# Sheet1.net
KiCad netlist of a schematic drawn in Altium Designer
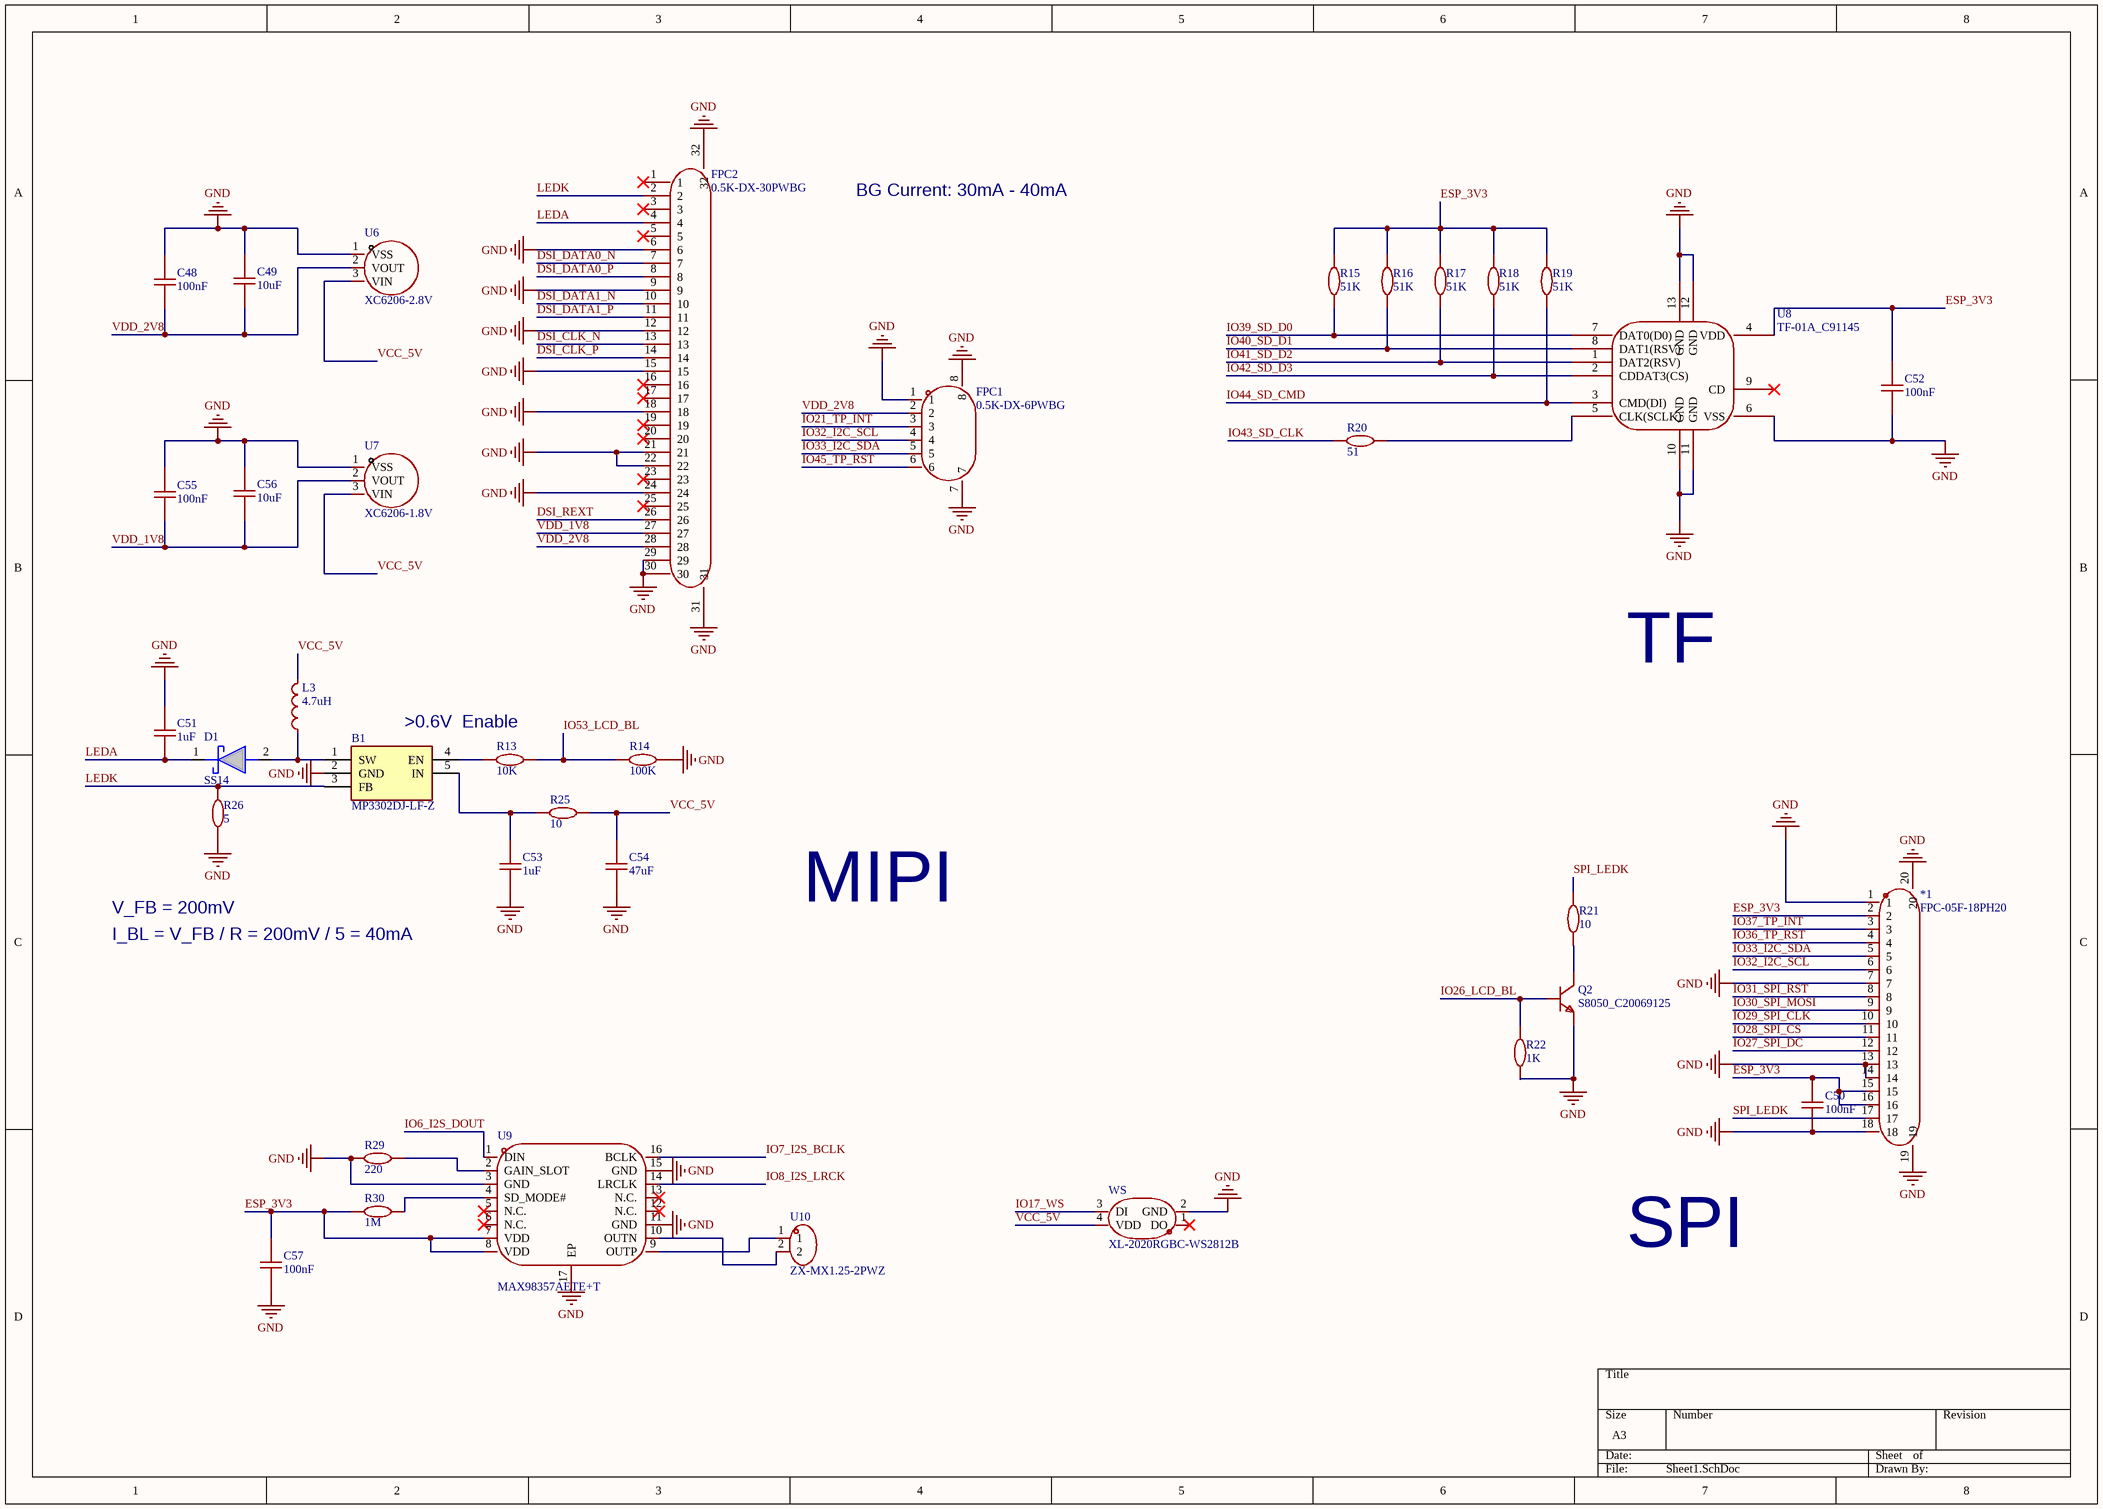
[diagram p0: Sheet1.SchDoc]

(export (version "E")
  (design (tool "Eeschema 10.0.6"))
  (components
    (comp (ref "*1")
      (value "FPC-05F-18PH20")
      (footprint "FPC-SMD_18P-P0.50_FPC-05F-18PH20")
      (libsource (lib "Connector") (part "FPC-05F-18PH20"))
    )
    (comp (ref "B1")
      (value "MP3302DJ-LF-Z")
      (footprint "SOT95P280X100-5N")
      (description "LED Lighting Drivers 1.3A, 1.3MHz WLED Driver")
      (fields (field (name "MOUSER PART NUMBER") "946-MP3302DJLFZ"))
      (libsource (lib "IC") (part "MP3302DJ-LF-Z"))
    )
    (comp (ref "C48") (value "100nF") (footprint "C0402") (libsource (lib "RLC") (part "C0402")))
    (comp (ref "C49") (value "10uF") (footprint "C0603") (libsource (lib "RLC") (part "C0603")))
    (comp (ref "C50") (value "100nF") (footprint "C0402") (libsource (lib "RLC") (part "C0402")))
    (comp (ref "C51") (value "1uF") (footprint "C0402") (libsource (lib "RLC") (part "C0402")))
    (comp (ref "C52") (value "100nF") (footprint "C0402") (libsource (lib "RLC") (part "C0402")))
    (comp (ref "C53") (value "1uF") (footprint "C0402") (libsource (lib "RLC") (part "C0402")))
    (comp (ref "C54") (value "47uF") (footprint "C0603") (libsource (lib "RLC") (part "C0603")))
    (comp (ref "C55") (value "100nF") (footprint "C0402") (libsource (lib "RLC") (part "C0402")))
    (comp (ref "C56") (value "10uF") (footprint "C0603") (libsource (lib "RLC") (part "C0603")))
    (comp (ref "C57") (value "100nF") (footprint "C0402") (libsource (lib "RLC") (part "C0402")))
    (comp (ref "D1")
      (value "SS14")
      (footprint "DIOM5126X250N")
      (description "TAIWAN SEMICONDUCTOR - SS14 - SCHOTTKY RECTIFIER, 1A, 40V, DO-214AC")
      (fields (field (name "MOUSER PART NUMBER") "821-SS14"))
      (libsource (lib "LED") (part "SS14"))
    )
    (comp (ref "FPC1")
      (value "0.5K-DX-6PWBG")
      (footprint "FPC-SMD_6P-P0.50_DEALON_0.5K-DX-6PWB")
      (libsource (lib "Connector") (part "0.5K-DX-6PWBG"))
    )
    (comp (ref "FPC2")
      (value "0.5K-DX-30PWBG")
      (footprint "FPC-SMD_6P-P0.50_DEALON_0.5K-DX-30PWB")
      (libsource (lib "Connector") (part "0.5K-DX-30PWBG"))
    )
    (comp (ref "L3") (value "4.7uH") (footprint "L0402-SMD") (libsource (lib "RLC") (part "L0402-SMD")))
    (comp (ref "Q2")
      (value "S8050_C20069125")
      (footprint "SOT-23-3_L2.9-W1.3-P1.90-LS2.3-BR")
      (libsource (lib "Transistor") (part "S8050_C20069125"))
    )
    (comp (ref "R13") (value "10K") (footprint "R0402") (libsource (lib "RLC") (part "R0402")))
    (comp (ref "R14") (value "100K") (footprint "R0402") (libsource (lib "RLC") (part "R0402")))
    (comp (ref "R15") (value "51K") (footprint "R0402") (libsource (lib "RLC") (part "R0402")))
    (comp (ref "R16") (value "51K") (footprint "R0402") (libsource (lib "RLC") (part "R0402")))
    (comp (ref "R17") (value "51K") (footprint "R0402") (libsource (lib "RLC") (part "R0402")))
    (comp (ref "R18") (value "51K") (footprint "R0402") (libsource (lib "RLC") (part "R0402")))
    (comp (ref "R19") (value "51K") (footprint "R0402") (libsource (lib "RLC") (part "R0402")))
    (comp (ref "R20") (value "51") (footprint "R0402") (libsource (lib "RLC") (part "R0402")))
    (comp (ref "R21") (value "10") (footprint "R0402") (libsource (lib "RLC") (part "R0402")))
    (comp (ref "R22") (value "1K") (footprint "R0402") (libsource (lib "RLC") (part "R0402")))
    (comp (ref "R25") (value "10") (footprint "R0402") (libsource (lib "RLC") (part "R0402")))
    (comp (ref "R26") (value "5") (footprint "R0402") (libsource (lib "RLC") (part "R0402")))
    (comp (ref "R29") (value "220") (footprint "R0402") (libsource (lib "RLC") (part "R0402")))
    (comp (ref "R30") (value "1M") (footprint "R0402") (libsource (lib "RLC") (part "R0402")))
    (comp (ref "U6")
      (value "XC6206-2.8V")
      (footprint "SOT-23-3_L2.9-W1.6-P1.90-LS2.8-BR")
      (libsource (lib "LDO") (part "XC6206-2.8V"))
    )
    (comp (ref "U7")
      (value "XC6206-1.8V")
      (footprint "SOT-23-3_L2.9-W1.6-P1.90-LS2.8-BR")
      (libsource (lib "LDO") (part "XC6206-2.8V"))
    )
    (comp (ref "U8")
      (value "TF-01A_C91145")
      (footprint "TF-SMD_TF-01A")
      (libsource (lib "IC") (part "TF-01A_C91145"))
    )
    (comp (ref "U9")
      (value "MAX98357AETE+T")
      (footprint "TQFN-16_L3.0-W3.0-P0.50-BL-EP1.5")
      (libsource (lib "IC") (part "MAX98357AETE+T"))
    )
    (comp (ref "U10")
      (value "ZX-MX1.25-2PWZ")
      (footprint "CONN-TH_2P-P1.25_ZX-MX1.25-2PWZ")
      (libsource (lib "Connector") (part "ZX-MX1.25-2PWZ"))
    )
    (comp (ref "WS")
      (value "XL-2020RGBC-WS2812B")
      (footprint "LED-SMD_4P-L2.0-W2.0-BR-1")
      (libsource (lib "IC") (part "XL-2020RGBC-WS2812B"))
    )
  )
  (nets
    (net (code "1") (name "/DSI_CLK_N") (class "Default")
      (node (ref "FPC2") (pin "13") (pinfunction "13_13") (pintype "passive"))
    )
    (net (code "2") (name "/DSI_CLK_P") (class "Default")
      (node (ref "FPC2") (pin "14") (pinfunction "14_14") (pintype "passive"))
    )
    (net (code "3") (name "/DSI_DATA0_N") (class "Default")
      (node (ref "FPC2") (pin "7") (pinfunction "7_7") (pintype "passive"))
    )
    (net (code "4") (name "/DSI_DATA0_P") (class "Default")
      (node (ref "FPC2") (pin "8") (pinfunction "8_8") (pintype "passive"))
    )
    (net (code "5") (name "/DSI_DATA1_N") (class "Default")
      (node (ref "FPC2") (pin "10") (pinfunction "10_10") (pintype "passive"))
    )
    (net (code "6") (name "/DSI_DATA1_P") (class "Default")
      (node (ref "FPC2") (pin "11") (pinfunction "11_11") (pintype "passive"))
    )
    (net (code "7") (name "/DSI_REXT") (class "Default")
      (node (ref "FPC2") (pin "26") (pinfunction "26_26") (pintype "passive"))
    )
    (net (code "8") (name "/ESP_3V3") (class "Default")
      (node (ref "*1") (pin "15") (pinfunction "15_15") (pintype "passive"))
      (node (ref "*1") (pin "16") (pinfunction "16_16") (pintype "passive"))
      (node (ref "*1") (pin "2") (pinfunction "2_2") (pintype "passive"))
      (node (ref "C50") (pin "2") (pinfunction "2_2") (pintype "passive"))
      (node (ref "C52") (pin "2") (pinfunction "2_2") (pintype "passive"))
      (node (ref "C57") (pin "2") (pinfunction "2_2") (pintype "passive"))
      (node (ref "R15") (pin "1") (pinfunction "1_1") (pintype "passive"))
      (node (ref "R16") (pin "1") (pinfunction "1_1") (pintype "passive"))
      (node (ref "R17") (pin "1") (pinfunction "1_1") (pintype "passive"))
      (node (ref "R18") (pin "1") (pinfunction "1_1") (pintype "passive"))
      (node (ref "R19") (pin "1") (pinfunction "1_1") (pintype "passive"))
      (node (ref "R30") (pin "1") (pinfunction "1_1") (pintype "passive"))
      (node (ref "U8") (pin "4") (pinfunction "VDD_4") (pintype "passive"))
      (node (ref "U9") (pin "7") (pinfunction "VDD_7") (pintype "passive"))
      (node (ref "U9") (pin "8") (pinfunction "VDD_8") (pintype "passive"))
    )
    (net (code "9") (name "/IO6_I2S_DOUT") (class "Default")
      (node (ref "U9") (pin "1") (pinfunction "DIN_1") (pintype "passive"))
    )
    (net (code "10") (name "/IO7_I2S_BCLK") (class "Default")
      (node (ref "U9") (pin "16") (pinfunction "BCLK_16") (pintype "passive"))
    )
    (net (code "11") (name "/IO8_I2S_LRCK") (class "Default")
      (node (ref "U9") (pin "14") (pinfunction "LRCLK_14") (pintype "passive"))
    )
    (net (code "12") (name "/IO17_WS") (class "Default")
      (node (ref "WS") (pin "3") (pinfunction "DI_3") (pintype "passive"))
    )
    (net (code "13") (name "/IO21_TP_INT") (class "Default")
      (node (ref "FPC1") (pin "3") (pinfunction "3_3") (pintype "passive"))
    )
    (net (code "14") (name "/IO26_LCD_BL") (class "Default")
      (node (ref "Q2") (pin "1") (pinfunction "B_1") (pintype "passive"))
      (node (ref "R22") (pin "2") (pinfunction "2_2") (pintype "passive"))
    )
    (net (code "15") (name "/IO27_SPI_DC") (class "Default")
      (node (ref "*1") (pin "12") (pinfunction "12_12") (pintype "passive"))
    )
    (net (code "16") (name "/IO28_SPI_CS") (class "Default")
      (node (ref "*1") (pin "11") (pinfunction "11_11") (pintype "passive"))
    )
    (net (code "17") (name "/IO29_SPI_CLK") (class "Default")
      (node (ref "*1") (pin "10") (pinfunction "10_10") (pintype "passive"))
    )
    (net (code "18") (name "/IO30_SPI_MOSI") (class "Default")
      (node (ref "*1") (pin "9") (pinfunction "9_9") (pintype "passive"))
    )
    (net (code "19") (name "/IO31_SPI_RST") (class "Default")
      (node (ref "*1") (pin "8") (pinfunction "8_8") (pintype "passive"))
    )
    (net (code "20") (name "/IO32_I2C_SCL") (class "Default")
      (node (ref "*1") (pin "6") (pinfunction "6_6") (pintype "passive"))
      (node (ref "FPC1") (pin "4") (pinfunction "4_4") (pintype "passive"))
    )
    (net (code "21") (name "/IO33_I2C_SDA") (class "Default")
      (node (ref "*1") (pin "5") (pinfunction "5_5") (pintype "passive"))
      (node (ref "FPC1") (pin "5") (pinfunction "5_5") (pintype "passive"))
    )
    (net (code "22") (name "/IO36_TP_RST") (class "Default")
      (node (ref "*1") (pin "4") (pinfunction "4_4") (pintype "passive"))
    )
    (net (code "23") (name "/IO37_TP_INT") (class "Default")
      (node (ref "*1") (pin "3") (pinfunction "3_3") (pintype "passive"))
    )
    (net (code "24") (name "/IO39_SD_D0") (class "Default")
      (node (ref "R15") (pin "2") (pinfunction "2_2") (pintype "passive"))
      (node (ref "U8") (pin "7") (pinfunction "DAT0(D0)_7") (pintype "passive"))
    )
    (net (code "25") (name "/IO40_SD_D1") (class "Default")
      (node (ref "R16") (pin "2") (pinfunction "2_2") (pintype "passive"))
      (node (ref "U8") (pin "8") (pinfunction "DAT1(RSV)_8") (pintype "passive"))
    )
    (net (code "26") (name "/IO41_SD_D2") (class "Default")
      (node (ref "R17") (pin "2") (pinfunction "2_2") (pintype "passive"))
      (node (ref "U8") (pin "1") (pinfunction "DAT2(RSV)_1") (pintype "passive"))
    )
    (net (code "27") (name "/IO42_SD_D3") (class "Default")
      (node (ref "R18") (pin "2") (pinfunction "2_2") (pintype "passive"))
      (node (ref "U8") (pin "2") (pinfunction "CDDAT3(CS)_2") (pintype "passive"))
    )
    (net (code "28") (name "/IO43_SD_CLK") (class "Default")
      (node (ref "R20") (pin "1") (pinfunction "1_1") (pintype "passive"))
    )
    (net (code "29") (name "/IO44_SD_CMD") (class "Default")
      (node (ref "R19") (pin "2") (pinfunction "2_2") (pintype "passive"))
      (node (ref "U8") (pin "3") (pinfunction "CMD(DI)_3") (pintype "passive"))
    )
    (net (code "30") (name "/IO45_TP_RST") (class "Default")
      (node (ref "FPC1") (pin "6") (pinfunction "6_6") (pintype "passive"))
    )
    (net (code "31") (name "/IO53_LCD_BL") (class "Default")
      (node (ref "R13") (pin "1") (pinfunction "1_1") (pintype "passive"))
      (node (ref "R14") (pin "2") (pinfunction "2_2") (pintype "passive"))
    )
    (net (code "32") (name "/LEDA") (class "Default")
      (node (ref "C51") (pin "1") (pinfunction "1_1") (pintype "passive"))
      (node (ref "D1") (pin "1") (pinfunction "K_1") (pintype "passive"))
      (node (ref "FPC2") (pin "4") (pinfunction "4_4") (pintype "passive"))
    )
    (net (code "33") (name "/LEDK") (class "Default")
      (node (ref "B1") (pin "3") (pinfunction "FB_3") (pintype "passive"))
      (node (ref "FPC2") (pin "2") (pinfunction "2_2") (pintype "passive"))
      (node (ref "R26") (pin "1") (pinfunction "1_1") (pintype "passive"))
    )
    (net (code "34") (name "/SPI_LEDK") (class "Default")
      (node (ref "*1") (pin "17") (pinfunction "17_17") (pintype "passive"))
      (node (ref "R21") (pin "2") (pinfunction "2_2") (pintype "passive"))
    )
    (net (code "35") (name "/VCC_5V") (class "Default")
      (node (ref "C54") (pin "2") (pinfunction "2_2") (pintype "passive"))
      (node (ref "L3") (pin "2") (pinfunction "2_2") (pintype "passive"))
      (node (ref "R25") (pin "1") (pinfunction "1_1") (pintype "passive"))
      (node (ref "U6") (pin "3") (pinfunction "VIN_3") (pintype "passive"))
      (node (ref "U7") (pin "3") (pinfunction "VIN_3") (pintype "passive"))
      (node (ref "WS") (pin "4") (pinfunction "VDD_4") (pintype "passive"))
    )
    (net (code "36") (name "/VDD_1V8") (class "Default")
      (node (ref "C55") (pin "1") (pinfunction "1_1") (pintype "passive"))
      (node (ref "C56") (pin "1") (pinfunction "1_1") (pintype "passive"))
      (node (ref "FPC2") (pin "27") (pinfunction "27_27") (pintype "passive"))
      (node (ref "U7") (pin "2") (pinfunction "VOUT_2") (pintype "passive"))
    )
    (net (code "37") (name "/VDD_2V8") (class "Default")
      (node (ref "C48") (pin "1") (pinfunction "1_1") (pintype "passive"))
      (node (ref "C49") (pin "1") (pinfunction "1_1") (pintype "passive"))
      (node (ref "FPC1") (pin "2") (pinfunction "2_2") (pintype "passive"))
      (node (ref "FPC2") (pin "28") (pinfunction "28_28") (pintype "passive"))
      (node (ref "U6") (pin "2") (pinfunction "VOUT_2") (pintype "passive"))
    )
    (net (code "38") (name "GND") (class "Default")
      (node (ref "*1") (pin "1") (pinfunction "1_1") (pintype "passive"))
      (node (ref "*1") (pin "13") (pinfunction "13_13") (pintype "passive"))
      (node (ref "*1") (pin "14") (pinfunction "14_14") (pintype "passive"))
      (node (ref "*1") (pin "18") (pinfunction "18_18") (pintype "passive"))
      (node (ref "*1") (pin "19") (pinfunction "19_19") (pintype "passive"))
      (node (ref "*1") (pin "20") (pinfunction "20_20") (pintype "passive"))
      (node (ref "*1") (pin "7") (pinfunction "7_7") (pintype "passive"))
      (node (ref "B1") (pin "2") (pinfunction "GND_2") (pintype "passive"))
      (node (ref "C48") (pin "2") (pinfunction "2_2") (pintype "passive"))
      (node (ref "C49") (pin "2") (pinfunction "2_2") (pintype "passive"))
      (node (ref "C50") (pin "1") (pinfunction "1_1") (pintype "passive"))
      (node (ref "C51") (pin "2") (pinfunction "2_2") (pintype "passive"))
      (node (ref "C52") (pin "1") (pinfunction "1_1") (pintype "passive"))
      (node (ref "C53") (pin "1") (pinfunction "1_1") (pintype "passive"))
      (node (ref "C54") (pin "1") (pinfunction "1_1") (pintype "passive"))
      (node (ref "C55") (pin "2") (pinfunction "2_2") (pintype "passive"))
      (node (ref "C56") (pin "2") (pinfunction "2_2") (pintype "passive"))
      (node (ref "C57") (pin "1") (pinfunction "1_1") (pintype "passive"))
      (node (ref "FPC1") (pin "1") (pinfunction "1_1") (pintype "passive"))
      (node (ref "FPC1") (pin "7") (pinfunction "7_7") (pintype "passive"))
      (node (ref "FPC1") (pin "8") (pinfunction "8_8") (pintype "passive"))
      (node (ref "FPC2") (pin "12") (pinfunction "12_12") (pintype "passive"))
      (node (ref "FPC2") (pin "15") (pinfunction "15_15") (pintype "passive"))
      (node (ref "FPC2") (pin "18") (pinfunction "18_18") (pintype "passive"))
      (node (ref "FPC2") (pin "21") (pinfunction "21_21") (pintype "passive"))
      (node (ref "FPC2") (pin "22") (pinfunction "22_22") (pintype "passive"))
      (node (ref "FPC2") (pin "24") (pinfunction "24_24") (pintype "passive"))
      (node (ref "FPC2") (pin "29") (pinfunction "29_29") (pintype "passive"))
      (node (ref "FPC2") (pin "30") (pinfunction "30_30") (pintype "passive"))
      (node (ref "FPC2") (pin "31") (pinfunction "31_31") (pintype "passive"))
      (node (ref "FPC2") (pin "32") (pinfunction "32_32") (pintype "passive"))
      (node (ref "FPC2") (pin "6") (pinfunction "6_6") (pintype "passive"))
      (node (ref "FPC2") (pin "9") (pinfunction "9_9") (pintype "passive"))
      (node (ref "Q2") (pin "2") (pinfunction "E_2") (pintype "passive"))
      (node (ref "R14") (pin "1") (pinfunction "1_1") (pintype "passive"))
      (node (ref "R22") (pin "1") (pinfunction "1_1") (pintype "passive"))
      (node (ref "R26") (pin "2") (pinfunction "2_2") (pintype "passive"))
      (node (ref "R29") (pin "1") (pinfunction "1_1") (pintype "passive"))
      (node (ref "U6") (pin "1") (pinfunction "VSS_1") (pintype "passive"))
      (node (ref "U7") (pin "1") (pinfunction "VSS_1") (pintype "passive"))
      (node (ref "U8") (pin "10") (pinfunction "GND_10") (pintype "passive"))
      (node (ref "U8") (pin "11") (pinfunction "GND_11") (pintype "passive"))
      (node (ref "U8") (pin "12") (pinfunction "GND_12") (pintype "passive"))
      (node (ref "U8") (pin "13") (pinfunction "GND_13") (pintype "passive"))
      (node (ref "U8") (pin "6") (pinfunction "VSS_6") (pintype "passive"))
      (node (ref "U9") (pin "11") (pinfunction "GND_11") (pintype "passive"))
      (node (ref "U9") (pin "15") (pinfunction "GND_15") (pintype "passive"))
      (node (ref "U9") (pin "17") (pinfunction "EP_17") (pintype "passive"))
      (node (ref "U9") (pin "3") (pinfunction "GND_3") (pintype "passive"))
      (node (ref "WS") (pin "2") (pinfunction "GND_2") (pintype "passive"))
    )
    (net (code "39") (name "Net-(B1-EN)") (class "Default")
      (node (ref "B1") (pin "4") (pinfunction "EN_4") (pintype "passive"))
      (node (ref "R13") (pin "2") (pinfunction "2_2") (pintype "passive"))
    )
    (net (code "40") (name "Net-(B1-IN)") (class "Default")
      (node (ref "B1") (pin "5") (pinfunction "IN_5") (pintype "passive"))
      (node (ref "C53") (pin "2") (pinfunction "2_2") (pintype "passive"))
      (node (ref "R25") (pin "2") (pinfunction "2_2") (pintype "passive"))
    )
    (net (code "41") (name "Net-(B1-SW)") (class "Default")
      (node (ref "B1") (pin "1") (pinfunction "SW_1") (pintype "passive"))
      (node (ref "D1") (pin "2") (pinfunction "A_2") (pintype "passive"))
      (node (ref "L3") (pin "1") (pinfunction "1_1") (pintype "passive"))
    )
    (net (code "42") (name "Net-(Q2-C)") (class "Default")
      (node (ref "Q2") (pin "3") (pinfunction "C_3") (pintype "passive"))
      (node (ref "R21") (pin "1") (pinfunction "1_1") (pintype "passive"))
    )
    (net (code "43") (name "Net-(U8-CLK(SCLK))") (class "Default")
      (node (ref "R20") (pin "2") (pinfunction "2_2") (pintype "passive"))
      (node (ref "U8") (pin "5") (pinfunction "CLK(SCLK)_5") (pintype "passive"))
    )
    (net (code "44") (name "Net-(U9-GAIN_SLOT)") (class "Default")
      (node (ref "R29") (pin "2") (pinfunction "2_2") (pintype "passive"))
      (node (ref "U9") (pin "2") (pinfunction "GAIN_SLOT_2") (pintype "passive"))
    )
    (net (code "45") (name "Net-(U9-OUTN)") (class "Default")
      (node (ref "U10") (pin "2") (pinfunction "2_2") (pintype "passive"))
      (node (ref "U9") (pin "10") (pinfunction "OUTN_10") (pintype "passive"))
    )
    (net (code "46") (name "Net-(U9-OUTP)") (class "Default")
      (node (ref "U10") (pin "1") (pinfunction "1_1") (pintype "passive"))
      (node (ref "U9") (pin "9") (pinfunction "OUTP_9") (pintype "passive"))
    )
    (net (code "47") (name "Net-(U9-SD_MODE#)") (class "Default")
      (node (ref "R30") (pin "2") (pinfunction "2_2") (pintype "passive"))
      (node (ref "U9") (pin "4") (pinfunction "SD_MODE#_4") (pintype "passive"))
    )
    (net (code "48") (name "unconnected-(FPC2-Pad1)") (class "Default")
      (node (ref "FPC2") (pin "1") (pinfunction "1_1") (pintype "passive+no_connect"))
    )
    (net (code "49") (name "unconnected-(FPC2-Pad3)") (class "Default")
      (node (ref "FPC2") (pin "3") (pinfunction "3_3") (pintype "passive+no_connect"))
    )
    (net (code "50") (name "unconnected-(FPC2-Pad5)") (class "Default")
      (node (ref "FPC2") (pin "5") (pinfunction "5_5") (pintype "passive+no_connect"))
    )
    (net (code "51") (name "unconnected-(FPC2-Pad16)") (class "Default")
      (node (ref "FPC2") (pin "16") (pinfunction "16_16") (pintype "passive+no_connect"))
    )
    (net (code "52") (name "unconnected-(FPC2-Pad17)") (class "Default")
      (node (ref "FPC2") (pin "17") (pinfunction "17_17") (pintype "passive+no_connect"))
    )
    (net (code "53") (name "unconnected-(FPC2-Pad19)") (class "Default")
      (node (ref "FPC2") (pin "19") (pinfunction "19_19") (pintype "passive+no_connect"))
    )
    (net (code "54") (name "unconnected-(FPC2-Pad20)") (class "Default")
      (node (ref "FPC2") (pin "20") (pinfunction "20_20") (pintype "passive+no_connect"))
    )
    (net (code "55") (name "unconnected-(FPC2-Pad23)") (class "Default")
      (node (ref "FPC2") (pin "23") (pinfunction "23_23") (pintype "passive+no_connect"))
    )
    (net (code "56") (name "unconnected-(FPC2-Pad25)") (class "Default")
      (node (ref "FPC2") (pin "25") (pinfunction "25_25") (pintype "passive+no_connect"))
    )
    (net (code "57") (name "unconnected-(U8-CD-Pad9)") (class "Default")
      (node (ref "U8") (pin "9") (pinfunction "CD_9") (pintype "passive+no_connect"))
    )
    (net (code "58") (name "unconnected-(U9-N.C.-Pad5)") (class "Default")
      (node (ref "U9") (pin "5") (pinfunction "N.C._5") (pintype "passive+no_connect"))
    )
    (net (code "59") (name "unconnected-(U9-N.C.-Pad6)") (class "Default")
      (node (ref "U9") (pin "6") (pinfunction "N.C._6") (pintype "passive+no_connect"))
    )
    (net (code "60") (name "unconnected-(U9-N.C.-Pad12)") (class "Default")
      (node (ref "U9") (pin "12") (pinfunction "N.C._12") (pintype "passive+no_connect"))
    )
    (net (code "61") (name "unconnected-(U9-N.C.-Pad13)") (class "Default")
      (node (ref "U9") (pin "13") (pinfunction "N.C._13") (pintype "passive+no_connect"))
    )
    (net (code "62") (name "unconnected-(WS-DO-Pad1)") (class "Default")
      (node (ref "WS") (pin "1") (pinfunction "DO_1") (pintype "passive+no_connect"))
    )
  )
)
